# power.net
KiCad netlist of a schematic drawn in EAGLE
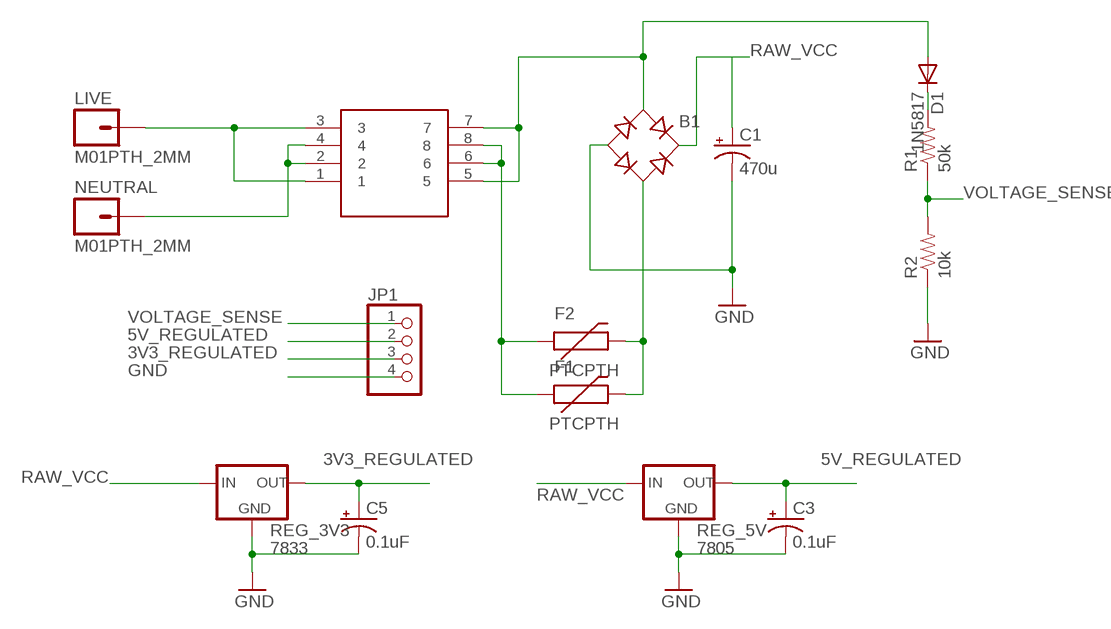
[diagram p0: schematic, sheet 1]

(export (version "E")
  (design (tool "Eeschema 10.0.6"))
  (components
    (comp (ref "B1")
      (value "RB1A")
      (footprint "eagle-import:RB1A")
      (libsource (lib "eagle-import") (part "RB1A"))
    )
    (comp (ref "C1")
      (value "470u")
      (footprint "eagle-import:E3,5-8")
      (libsource (lib "eagle-import") (part "CPOL-USE3.5-8"))
    )
    (comp (ref "C3")
      (value "0.1uF")
      (footprint "eagle-import:CPOL-RADIAL-10UF-25V")
      (libsource (lib "eagle-import") (part "10UF-25V-20%(PTH)"))
    )
    (comp (ref "C5")
      (value "0.1uF")
      (footprint "eagle-import:CPOL-RADIAL-10UF-25V")
      (libsource (lib "eagle-import") (part "10UF-25V-20%(PTH)"))
    )
    (comp (ref "D1")
      (value "1N5817")
      (footprint "eagle-import:DO34-7")
      (libsource (lib "eagle-import") (part "BAS15"))
    )
    (comp (ref "F1")
      (value "PTCPTH")
      (footprint "eagle-import:PTC")
      (libsource (lib "eagle-import") (part "PTCPTH"))
    )
    (comp (ref "F2")
      (value "PTCPTH")
      (footprint "eagle-import:PTC")
      (libsource (lib "eagle-import") (part "PTCPTH"))
    )
    (comp (ref "JP1")
      (value "PINHD-1X4")
      (footprint "eagle-import:1X04")
      (libsource (lib "eagle-import") (part "PINHD-1X4"))
    )
    (comp (ref "LIVE")
      (value "M01PTH_2MM")
      (footprint "eagle-import:1X01_2MM")
      (libsource (lib "eagle-import") (part "M01PTH_2MM"))
    )
    (comp (ref "NEUTRAL")
      (value "M01PTH_2MM")
      (footprint "eagle-import:1X01_2MM")
      (libsource (lib "eagle-import") (part "M01PTH_2MM"))
    )
    (comp (ref "R1")
      (value "50k")
      (footprint "eagle-import:AXIAL-0.3EZ")
      (libsource (lib "eagle-import") (part "RESISTOREZ"))
    )
    (comp (ref "R2")
      (value "10k")
      (footprint "eagle-import:AXIAL-0.3EZ")
      (libsource (lib "eagle-import") (part "RESISTOREZ"))
    )
    (comp (ref "REG_3V3")
      (value "7833")
      (footprint "eagle-import:TO220-IGO")
      (libsource (lib "eagle-import") (part "V_REG_78XXSINK"))
    )
    (comp (ref "REG_5V")
      (value "7805")
      (footprint "eagle-import:TO220-IGO")
      (libsource (lib "eagle-import") (part "V_REG_78XXSINK"))
    )
    (comp (ref "U$1")
      (value "FP16-150")
      (footprint "eagle-import:FLATPACKXFORMER")
      (libsource (lib "eagle-import") (part "FLATPACKXFORMER"))
    )
  )
  (nets
    (net (code "1") (name "/3V3_REGULATED") (class "Default")
      (node (ref "C5") (pin "1") (pinfunction "+_1") (pintype "passive"))
      (node (ref "JP1") (pin "3") (pinfunction "3_3") (pintype "passive"))
      (node (ref "REG_3V3") (pin "OUT") (pinfunction "OUT_OUT") (pintype "output"))
    )
    (net (code "2") (name "/5V_REGULATED") (class "Default")
      (node (ref "C3") (pin "1") (pinfunction "+_1") (pintype "passive"))
      (node (ref "JP1") (pin "2") (pinfunction "2_2") (pintype "passive"))
      (node (ref "REG_5V") (pin "OUT") (pinfunction "OUT_OUT") (pintype "output"))
    )
    (net (code "3") (name "/RAW_VCC") (class "Default")
      (node (ref "B1") (pin "+") (pinfunction "+_+") (pintype "passive"))
      (node (ref "C1") (pin "+") (pinfunction "+_+") (pintype "passive"))
      (node (ref "REG_3V3") (pin "IN") (pinfunction "IN_IN") (pintype "input"))
      (node (ref "REG_5V") (pin "IN") (pinfunction "IN_IN") (pintype "input"))
    )
    (net (code "4") (name "/VOLTAGE_SENSE") (class "Default")
      (node (ref "JP1") (pin "1") (pinfunction "1_1") (pintype "passive"))
      (node (ref "R1") (pin "P$1") (pinfunction "1_P$1") (pintype "passive"))
      (node (ref "R2") (pin "P$2") (pinfunction "2_P$2") (pintype "passive"))
    )
    (net (code "5") (name "GND") (class "Default")
      (node (ref "B1") (pin "-") (pinfunction "-_-") (pintype "passive"))
      (node (ref "C1") (pin "-") (pinfunction "-_-") (pintype "passive"))
      (node (ref "C3") (pin "2") (pinfunction "-_2") (pintype "passive"))
      (node (ref "C5") (pin "2") (pinfunction "-_2") (pintype "passive"))
      (node (ref "JP1") (pin "4") (pinfunction "4_4") (pintype "passive"))
      (node (ref "R2") (pin "P$1") (pinfunction "1_P$1") (pintype "passive"))
      (node (ref "REG_3V3") (pin "GND") (pinfunction "GND_GND") (pintype "input"))
      (node (ref "REG_5V") (pin "GND") (pinfunction "GND_GND") (pintype "input"))
    )
    (net (code "6") (name "Net-(B1-PadAC1)") (class "Default")
      (node (ref "B1") (pin "AC1") (pinfunction "AC1_AC1") (pintype "passive"))
      (node (ref "D1") (pin "A") (pinfunction "A_A") (pintype "passive"))
      (node (ref "U$1") (pin "5") (pinfunction "5_5") (pintype "bidirectional"))
      (node (ref "U$1") (pin "7") (pinfunction "7_7") (pintype "bidirectional"))
    )
    (net (code "7") (name "Net-(F1-1)") (class "Default")
      (node (ref "F1") (pin "P$1") (pinfunction "1_P$1") (pintype "bidirectional"))
      (node (ref "F2") (pin "P$1") (pinfunction "1_P$1") (pintype "bidirectional"))
      (node (ref "U$1") (pin "6") (pinfunction "6_6") (pintype "bidirectional"))
      (node (ref "U$1") (pin "8") (pinfunction "8_8") (pintype "bidirectional"))
    )
    (net (code "8") (name "Net-(F1-2)") (class "Default")
      (node (ref "B1") (pin "AC2") (pinfunction "AC2_AC2") (pintype "passive"))
      (node (ref "F1") (pin "P$2") (pinfunction "2_P$2") (pintype "bidirectional"))
      (node (ref "F2") (pin "P$2") (pinfunction "2_P$2") (pintype "bidirectional"))
    )
    (net (code "9") (name "Net-(LIVE-Pad1)") (class "Default")
      (node (ref "LIVE") (pin "1") (pinfunction "1_1") (pintype "passive"))
      (node (ref "U$1") (pin "1") (pinfunction "1_1") (pintype "bidirectional"))
      (node (ref "U$1") (pin "3") (pinfunction "3_3") (pintype "bidirectional"))
    )
    (net (code "10") (name "Net-(NEUTRAL-Pad1)") (class "Default")
      (node (ref "NEUTRAL") (pin "1") (pinfunction "1_1") (pintype "passive"))
      (node (ref "U$1") (pin "2") (pinfunction "2_2") (pintype "bidirectional"))
      (node (ref "U$1") (pin "4") (pinfunction "4_4") (pintype "bidirectional"))
    )
    (net (code "11") (name "Net-(R1-2)") (class "Default")
      (node (ref "D1") (pin "C") (pinfunction "C_C") (pintype "passive"))
      (node (ref "R1") (pin "P$2") (pinfunction "2_P$2") (pintype "passive"))
    )
  )
)
